# Sheet_WallSwitch_TOP.net
KiCad netlist of a schematic drawn in Altium Designer
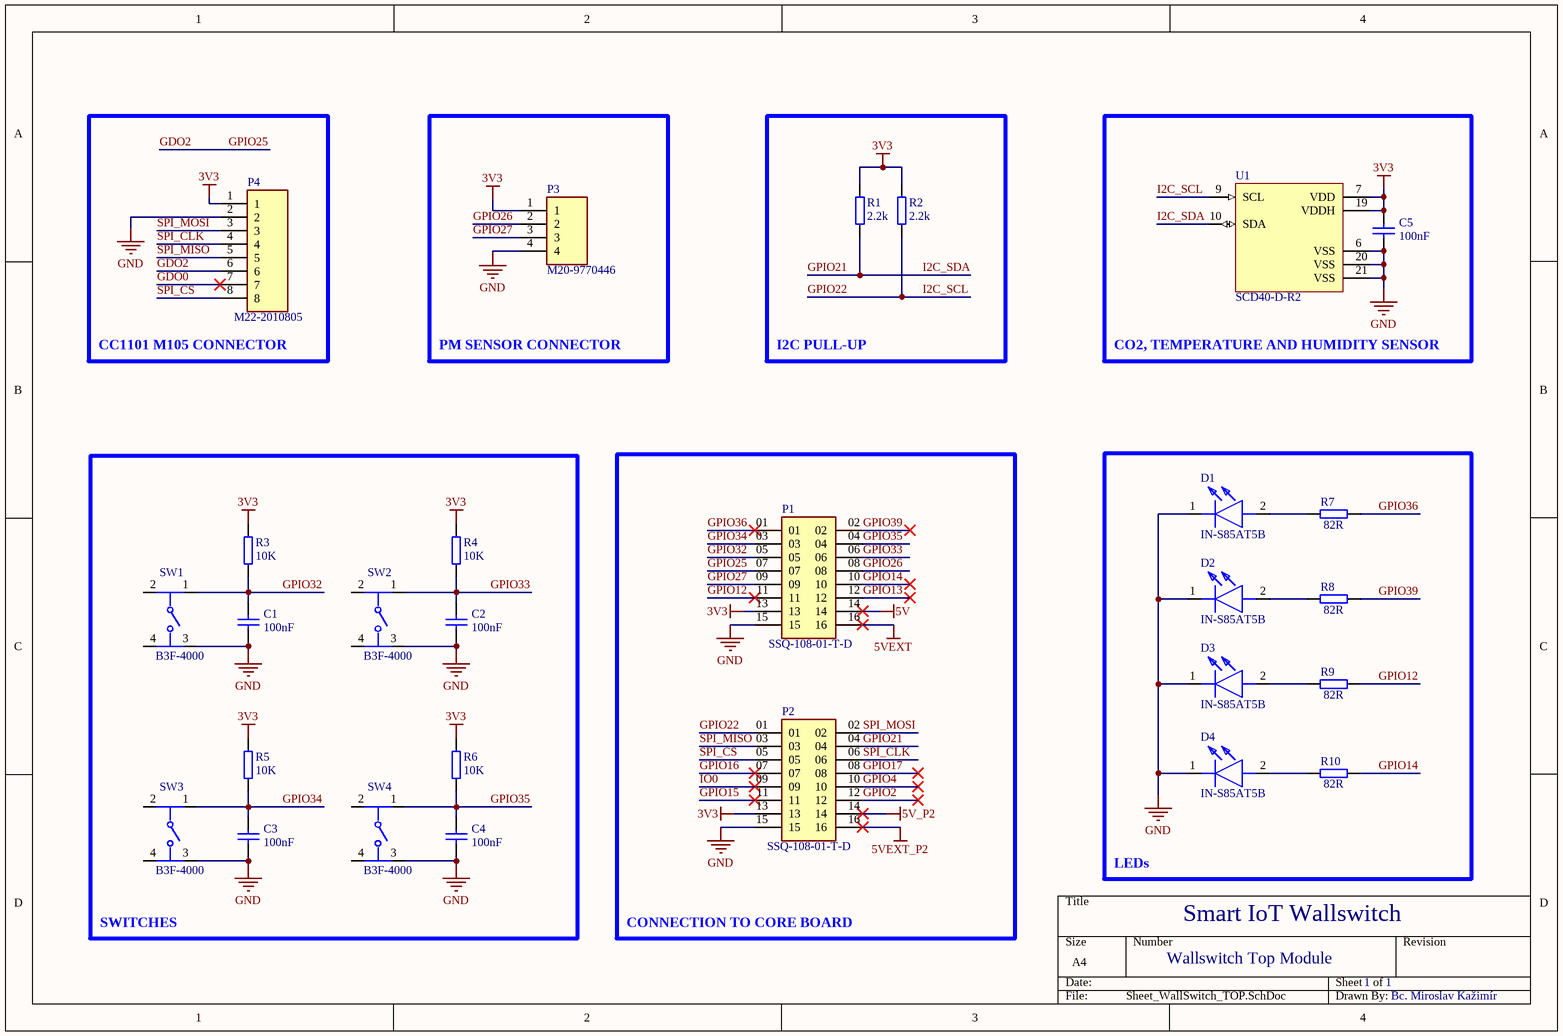
[diagram p0: Sheet_WallSwitch_TOP.SchDoc]

(export (version "E")
  (design (tool "Eeschema 10.0.6"))
  (components
    (comp (ref "C1")
      (value "C0805C104K5RAC7411")
      (footprint "FP-C0805C-DN-IPC_A")
      (description "Cap Ceramic 0.1uF 50V X7R 10% SMD 0805 125°C Paper T/R")
      (fields
        (field (name "MANUFACTURER") "KEMET")
        (field (name "TOLERANCE") "10%")
        (field (name "CAPACITANCE") "100nF")
      )
      (libsource (lib "Schlib1") (part "C0805C104K5RAC7411"))
    )
    (comp (ref "C2")
      (value "C0805C104K5RAC7411")
      (footprint "FP-C0805C-DN-IPC_A")
      (description "Cap Ceramic 0.1uF 50V X7R 10% SMD 0805 125°C Paper T/R")
      (fields
        (field (name "MANUFACTURER") "KEMET")
        (field (name "TOLERANCE") "10%")
        (field (name "CAPACITANCE") "100nF")
      )
      (libsource (lib "Schlib1") (part "C0805C104K5RAC7411"))
    )
    (comp (ref "C3")
      (value "C0805C104K5RAC7411")
      (footprint "FP-C0805C-DN-IPC_A")
      (description "Cap Ceramic 0.1uF 50V X7R 10% SMD 0805 125°C Paper T/R")
      (fields
        (field (name "MANUFACTURER") "KEMET")
        (field (name "TOLERANCE") "10%")
        (field (name "CAPACITANCE") "100nF")
      )
      (libsource (lib "Schlib1") (part "C0805C104K5RAC7411"))
    )
    (comp (ref "C4")
      (value "C0805C104K5RAC7411")
      (footprint "FP-C0805C-DN-IPC_A")
      (description "Cap Ceramic 0.1uF 50V X7R 10% SMD 0805 125°C Paper T/R")
      (fields
        (field (name "MANUFACTURER") "KEMET")
        (field (name "TOLERANCE") "10%")
        (field (name "CAPACITANCE") "100nF")
      )
      (libsource (lib "Schlib1") (part "C0805C104K5RAC7411"))
    )
    (comp (ref "C5")
      (value "C0805C104K5RAC7411")
      (footprint "FP-C0805C-DN-IPC_A")
      (description "Cap Ceramic 0.1uF 50V X7R 10% SMD 0805 125°C Paper T/R")
      (fields
        (field (name "MANUFACTURER") "KEMET")
        (field (name "TOLERANCE") "10%")
        (field (name "CAPACITANCE") "100nF")
      )
      (libsource (lib "Schlib1") (part "C0805C104K5RAC7411"))
    )
    (comp (ref "D1")
      (value "IN-S85AT5B")
      (footprint "LEDC2012X110N")
      (description "Led Blue Clear 0805 SMD")
      (fields (field (name "MANUFACTURER") "Inolux"))
      (libsource (lib "Schlib1") (part "IN-S85AT5B"))
    )
    (comp (ref "D2")
      (value "IN-S85AT5B")
      (footprint "LEDC2012X110N")
      (description "Led Blue Clear 0805 SMD")
      (fields (field (name "MANUFACTURER") "Inolux"))
      (libsource (lib "Schlib1") (part "IN-S85AT5B"))
    )
    (comp (ref "D3")
      (value "IN-S85AT5B")
      (footprint "LEDC2012X110N")
      (description "Led Blue Clear 0805 SMD")
      (fields (field (name "MANUFACTURER") "Inolux"))
      (libsource (lib "Schlib1") (part "IN-S85AT5B"))
    )
    (comp (ref "D4")
      (value "IN-S85AT5B")
      (footprint "LEDC2012X110N")
      (description "Led Blue Clear 0805 SMD")
      (fields (field (name "MANUFACTURER") "Inolux"))
      (libsource (lib "Schlib1") (part "IN-S85AT5B"))
    )
    (comp (ref "P1")
      (value "SSQ-108-01-T-D")
      (footprint "SAMTEC_SSQ-108-XX-X-D")
      (description "Headers & Wire Housings Tiger Buy Socket Strip with Square Tails, 0.100 Pitch")
      (fields (field (name "MANUFACTURER") "Samtec"))
      (libsource (lib "Schlib1") (part "SSQ-108-01-T-D"))
    )
    (comp (ref "P2")
      (value "SSQ-108-01-T-D")
      (footprint "SAMTEC_SSQ-108-XX-X-D")
      (description "Headers & Wire Housings Tiger Buy Socket Strip with Square Tails, 0.100 Pitch")
      (fields (field (name "MANUFACTURER") "Samtec"))
      (libsource (lib "Schlib1") (part "SSQ-108-01-T-D"))
    )
    (comp (ref "P3")
      (value "M20-9770446")
      (footprint "HDRV4W64P0X254_1X4_1016X254X834P")
      (description "04 SIL VERT PIN HDR")
      (fields (field (name "MANUFACTURER") "Harwin"))
      (libsource (lib "Schlib1") (part "M20-9770446"))
    )
    (comp (ref "P4")
      (value "M22-2010805")
      (footprint "HDRV8W60P0X200_1X8_1600X200X525P")
      (description "Connector, Header, 8Pos, 1Row, 2Mm Rohs Compliant: Yes")
      (fields (field (name "MANUFACTURER") "Harwin"))
      (libsource (lib "RPiZeroShield") (part "M22-2010805"))
    )
    (comp (ref "R1")
      (value "RCC12062K20FKEA")
      (footprint "RCC1206_e3")
      (description "Res, Aec-Q200, 2K2, 1%, 0.5W, 1206 Rohs Compliant: Yes")
      (fields (field (name "MANUFACTURER") "Vishay") (field (name "RESISTANCE") "2.2k"))
      (libsource (lib "Schlib1") (part "RCC12062K20FKEA"))
    )
    (comp (ref "R2")
      (value "RCC12062K20FKEA")
      (footprint "RCC1206_e3")
      (description "Res, Aec-Q200, 2K2, 1%, 0.5W, 1206 Rohs Compliant: Yes")
      (fields (field (name "MANUFACTURER") "Vishay") (field (name "RESISTANCE") "2.2k"))
      (libsource (lib "Schlib1") (part "RCC12062K20FKEA"))
    )
    (comp (ref "R3")
      (value "ERJ-UP6J103V")
      (footprint "RESC2012X70N")
      (description "Res 10K Ohm 5% 1/2W 0805")
      (fields (field (name "MANUFACTURER") "Panasonic") (field (name "RESISTANCE") "10K"))
      (libsource (lib "Schlib1") (part "ERJ-UP6J103V"))
    )
    (comp (ref "R4")
      (value "ERJ-UP6J103V")
      (footprint "RESC2012X70N")
      (description "Res 10K Ohm 5% 1/2W 0805")
      (fields (field (name "MANUFACTURER") "Panasonic") (field (name "RESISTANCE") "10K"))
      (libsource (lib "Schlib1") (part "ERJ-UP6J103V"))
    )
    (comp (ref "R5")
      (value "ERJ-UP6J103V")
      (footprint "RESC2012X70N")
      (description "Res 10K Ohm 5% 1/2W 0805")
      (fields (field (name "MANUFACTURER") "Panasonic") (field (name "RESISTANCE") "10K"))
      (libsource (lib "Schlib1") (part "ERJ-UP6J103V"))
    )
    (comp (ref "R6")
      (value "ERJ-UP6J103V")
      (footprint "RESC2012X70N")
      (description "Res 10K Ohm 5% 1/2W 0805")
      (fields (field (name "MANUFACTURER") "Panasonic") (field (name "RESISTANCE") "10K"))
      (libsource (lib "Schlib1") (part "ERJ-UP6J103V"))
    )
    (comp (ref "R7")
      (value "ESR10EZPJ820")
      (footprint "FP-ESR10-IPC_A")
      (description "Res Thick Film 0805 82 Ohm 5% 0.4W ±200ppm/C Epoxy Resin Pad SMD Automotive T/R")
      (fields
        (field (name "MANUFACTURER") "Rohm")
        (field (name "RESISTANCE") "82R")
        (field (name "TOLERANCE") "5%")
      )
      (libsource (lib "Schlib1") (part "ESR10EZPJ820"))
    )
    (comp (ref "R8")
      (value "ESR10EZPJ820")
      (footprint "FP-ESR10-IPC_A")
      (description "Res Thick Film 0805 82 Ohm 5% 0.4W ±200ppm/C Epoxy Resin Pad SMD Automotive T/R")
      (fields
        (field (name "MANUFACTURER") "Rohm")
        (field (name "RESISTANCE") "82R")
        (field (name "TOLERANCE") "5%")
      )
      (libsource (lib "Schlib1") (part "ESR10EZPJ820"))
    )
    (comp (ref "R9")
      (value "ESR10EZPJ820")
      (footprint "FP-ESR10-IPC_A")
      (description "Res Thick Film 0805 82 Ohm 5% 0.4W ±200ppm/C Epoxy Resin Pad SMD Automotive T/R")
      (fields
        (field (name "MANUFACTURER") "Rohm")
        (field (name "RESISTANCE") "82R")
        (field (name "TOLERANCE") "5%")
      )
      (libsource (lib "Schlib1") (part "ESR10EZPJ820"))
    )
    (comp (ref "R10")
      (value "ESR10EZPJ820")
      (footprint "FP-ESR10-IPC_A")
      (description "Res Thick Film 0805 82 Ohm 5% 0.4W ±200ppm/C Epoxy Resin Pad SMD Automotive T/R")
      (fields
        (field (name "MANUFACTURER") "Rohm")
        (field (name "RESISTANCE") "82R")
        (field (name "TOLERANCE") "5%")
      )
      (libsource (lib "Schlib1") (part "ESR10EZPJ820"))
    )
    (comp (ref "SW1")
      (value "B3F-4000")
      (footprint "FP-B3F-4000-MFG")
      (description "SWITCH TACTILE SPST-NO 0.05A 24V")
      (fields (field (name "MANUFACTURER") "Omron"))
      (libsource (lib "Schlib1") (part "B3F-4000"))
    )
    (comp (ref "SW2")
      (value "B3F-4000")
      (footprint "FP-B3F-4000-MFG")
      (description "SWITCH TACTILE SPST-NO 0.05A 24V")
      (fields (field (name "MANUFACTURER") "Omron"))
      (libsource (lib "Schlib1") (part "B3F-4000"))
    )
    (comp (ref "SW3")
      (value "B3F-4000")
      (footprint "FP-B3F-4000-MFG")
      (description "SWITCH TACTILE SPST-NO 0.05A 24V")
      (fields (field (name "MANUFACTURER") "Omron"))
      (libsource (lib "Schlib1") (part "B3F-4000"))
    )
    (comp (ref "SW4")
      (value "B3F-4000")
      (footprint "FP-B3F-4000-MFG")
      (description "SWITCH TACTILE SPST-NO 0.05A 24V")
      (fields (field (name "MANUFACTURER") "Omron"))
      (libsource (lib "Schlib1") (part "B3F-4000"))
    )
    (comp (ref "U1")
      (value "SCD40-D-R2")
      (footprint "SCD4x")
      (description "SCD40-D-R2 CO2 Sensor I2C, SMD ToR 600 pcs")
      (fields (field (name "MANUFACTURER") "Sensirion"))
      (libsource (lib "Schlib1") (part "SCD40-D-R2"))
    )
  )
  (nets
    (net (code "1") (name "/GDO0") (class "Default")
      (node (ref "P4") (pin "7") (pinfunction "7_7") (pintype "passive+no_connect"))
    )
    (net (code "2") (name "/GDO2") (class "Default")
      (node (ref "P1") (pin "07") (pinfunction "07_07") (pintype "passive"))
      (node (ref "P4") (pin "6") (pinfunction "6_6") (pintype "passive"))
    )
    (net (code "3") (name "/GPIO2") (class "Default")
      (node (ref "P2") (pin "12") (pinfunction "12_12") (pintype "passive+no_connect"))
    )
    (net (code "4") (name "/GPIO4") (class "Default")
      (node (ref "P2") (pin "10") (pinfunction "10_10") (pintype "passive+no_connect"))
    )
    (net (code "5") (name "/GPIO12") (class "Default")
      (node (ref "P1") (pin "11") (pinfunction "11_11") (pintype "passive"))
      (node (ref "R9") (pin "2") (pinfunction "2_2") (pintype "passive"))
    )
    (net (code "6") (name "/GPIO13") (class "Default")
      (node (ref "P1") (pin "12") (pinfunction "12_12") (pintype "passive+no_connect"))
    )
    (net (code "7") (name "/GPIO14") (class "Default")
      (node (ref "P1") (pin "10") (pinfunction "10_10") (pintype "passive"))
      (node (ref "R10") (pin "2") (pinfunction "2_2") (pintype "passive"))
    )
    (net (code "8") (name "/GPIO15") (class "Default")
      (node (ref "P2") (pin "11") (pinfunction "11_11") (pintype "passive+no_connect"))
    )
    (net (code "9") (name "/GPIO16") (class "Default")
      (node (ref "P2") (pin "07") (pinfunction "07_07") (pintype "passive+no_connect"))
    )
    (net (code "10") (name "/GPIO17") (class "Default")
      (node (ref "P2") (pin "08") (pinfunction "08_08") (pintype "passive+no_connect"))
    )
    (net (code "11") (name "/GPIO21") (class "Default")
      (node (ref "P2") (pin "04") (pinfunction "04_04") (pintype "passive"))
      (node (ref "R1") (pin "1") (pinfunction "1_1") (pintype "passive"))
      (node (ref "U1") (pin "10") (pinfunction "SDA_10") (pintype "bidirectional"))
    )
    (net (code "12") (name "/GPIO22") (class "Default")
      (node (ref "P2") (pin "01") (pinfunction "01_01") (pintype "passive"))
      (node (ref "R2") (pin "1") (pinfunction "1_1") (pintype "passive"))
      (node (ref "U1") (pin "9") (pinfunction "SCL_9") (pintype "input"))
    )
    (net (code "13") (name "/GPIO26") (class "Default")
      (node (ref "P1") (pin "08") (pinfunction "08_08") (pintype "passive"))
      (node (ref "P3") (pin "2") (pinfunction "2_2") (pintype "passive"))
    )
    (net (code "14") (name "/GPIO27") (class "Default")
      (node (ref "P1") (pin "09") (pinfunction "09_09") (pintype "passive"))
      (node (ref "P3") (pin "3") (pinfunction "3_3") (pintype "passive"))
    )
    (net (code "15") (name "/GPIO32") (class "Default")
      (node (ref "C1") (pin "1") (pinfunction "1_1") (pintype "passive"))
      (node (ref "P1") (pin "05") (pinfunction "05_05") (pintype "passive"))
      (node (ref "R3") (pin "2") (pinfunction "2_2") (pintype "passive"))
      (node (ref "SW1") (pin "1") (pinfunction "1_1") (pintype "passive"))
    )
    (net (code "16") (name "/GPIO33") (class "Default")
      (node (ref "C2") (pin "1") (pinfunction "1_1") (pintype "passive"))
      (node (ref "P1") (pin "06") (pinfunction "06_06") (pintype "passive"))
      (node (ref "R4") (pin "2") (pinfunction "2_2") (pintype "passive"))
      (node (ref "SW2") (pin "1") (pinfunction "1_1") (pintype "passive"))
    )
    (net (code "17") (name "/GPIO34") (class "Default")
      (node (ref "C3") (pin "1") (pinfunction "1_1") (pintype "passive"))
      (node (ref "P1") (pin "03") (pinfunction "03_03") (pintype "passive"))
      (node (ref "R5") (pin "2") (pinfunction "2_2") (pintype "passive"))
      (node (ref "SW3") (pin "1") (pinfunction "1_1") (pintype "passive"))
    )
    (net (code "18") (name "/GPIO35") (class "Default")
      (node (ref "C4") (pin "1") (pinfunction "1_1") (pintype "passive"))
      (node (ref "P1") (pin "04") (pinfunction "04_04") (pintype "passive"))
      (node (ref "R6") (pin "2") (pinfunction "2_2") (pintype "passive"))
      (node (ref "SW4") (pin "1") (pinfunction "1_1") (pintype "passive"))
    )
    (net (code "19") (name "/GPIO36") (class "Default")
      (node (ref "P1") (pin "01") (pinfunction "01_01") (pintype "passive"))
      (node (ref "R7") (pin "2") (pinfunction "2_2") (pintype "passive"))
    )
    (net (code "20") (name "/GPIO39") (class "Default")
      (node (ref "P1") (pin "02") (pinfunction "02_02") (pintype "passive"))
      (node (ref "R8") (pin "2") (pinfunction "2_2") (pintype "passive"))
    )
    (net (code "21") (name "/IO0") (class "Default")
      (node (ref "P2") (pin "09") (pinfunction "09_09") (pintype "passive+no_connect"))
    )
    (net (code "22") (name "/SPI_CLK") (class "Default")
      (node (ref "P2") (pin "06") (pinfunction "06_06") (pintype "passive"))
      (node (ref "P4") (pin "4") (pinfunction "4_4") (pintype "passive"))
    )
    (net (code "23") (name "/SPI_CS") (class "Default")
      (node (ref "P2") (pin "05") (pinfunction "05_05") (pintype "passive"))
      (node (ref "P4") (pin "8") (pinfunction "8_8") (pintype "passive"))
    )
    (net (code "24") (name "/SPI_MISO") (class "Default")
      (node (ref "P2") (pin "03") (pinfunction "03_03") (pintype "passive"))
      (node (ref "P4") (pin "5") (pinfunction "5_5") (pintype "passive"))
    )
    (net (code "25") (name "/SPI_MOSI") (class "Default")
      (node (ref "P2") (pin "02") (pinfunction "02_02") (pintype "passive"))
      (node (ref "P4") (pin "3") (pinfunction "3_3") (pintype "passive"))
    )
    (net (code "26") (name "3V3") (class "Default")
      (node (ref "C5") (pin "1") (pinfunction "1_1") (pintype "passive"))
      (node (ref "P1") (pin "13") (pinfunction "13_13") (pintype "passive"))
      (node (ref "P2") (pin "13") (pinfunction "13_13") (pintype "passive"))
      (node (ref "P3") (pin "1") (pinfunction "1_1") (pintype "passive"))
      (node (ref "P4") (pin "1") (pinfunction "1_1") (pintype "passive"))
      (node (ref "R1") (pin "2") (pinfunction "2_2") (pintype "passive"))
      (node (ref "R2") (pin "2") (pinfunction "2_2") (pintype "passive"))
      (node (ref "R3") (pin "1") (pinfunction "1_1") (pintype "passive"))
      (node (ref "R4") (pin "1") (pinfunction "1_1") (pintype "passive"))
      (node (ref "R5") (pin "1") (pinfunction "1_1") (pintype "passive"))
      (node (ref "R6") (pin "1") (pinfunction "1_1") (pintype "passive"))
      (node (ref "U1") (pin "19") (pinfunction "VDDH_19") (pintype "power_in"))
      (node (ref "U1") (pin "7") (pinfunction "VDD_7") (pintype "power_in"))
    )
    (net (code "27") (name "5V") (class "Default")
      (node (ref "P1") (pin "14") (pinfunction "14_14") (pintype "passive"))
    )
    (net (code "28") (name "5VEXT") (class "Default")
      (node (ref "P1") (pin "16") (pinfunction "16_16") (pintype "passive"))
    )
    (net (code "29") (name "5VEXT_P2") (class "Default")
      (node (ref "P2") (pin "16") (pinfunction "16_16") (pintype "passive"))
    )
    (net (code "30") (name "5V_P2") (class "Default")
      (node (ref "P2") (pin "14") (pinfunction "14_14") (pintype "passive"))
    )
    (net (code "31") (name "GND") (class "Default")
      (node (ref "C1") (pin "2") (pinfunction "2_2") (pintype "passive"))
      (node (ref "C2") (pin "2") (pinfunction "2_2") (pintype "passive"))
      (node (ref "C3") (pin "2") (pinfunction "2_2") (pintype "passive"))
      (node (ref "C4") (pin "2") (pinfunction "2_2") (pintype "passive"))
      (node (ref "C5") (pin "2") (pinfunction "2_2") (pintype "passive"))
      (node (ref "D1") (pin "1") (pinfunction "K_1") (pintype "passive"))
      (node (ref "D2") (pin "1") (pinfunction "K_1") (pintype "passive"))
      (node (ref "D3") (pin "1") (pinfunction "K_1") (pintype "passive"))
      (node (ref "D4") (pin "1") (pinfunction "K_1") (pintype "passive"))
      (node (ref "P1") (pin "15") (pinfunction "15_15") (pintype "passive"))
      (node (ref "P2") (pin "15") (pinfunction "15_15") (pintype "passive"))
      (node (ref "P3") (pin "4") (pinfunction "4_4") (pintype "passive"))
      (node (ref "P4") (pin "2") (pinfunction "2_2") (pintype "passive"))
      (node (ref "SW1") (pin "3") (pinfunction "3_3") (pintype "passive"))
      (node (ref "SW2") (pin "3") (pinfunction "3_3") (pintype "passive"))
      (node (ref "SW3") (pin "3") (pinfunction "3_3") (pintype "passive"))
      (node (ref "SW4") (pin "3") (pinfunction "3_3") (pintype "passive"))
      (node (ref "U1") (pin "20") (pinfunction "VSS_20") (pintype "power_in"))
      (node (ref "U1") (pin "21") (pinfunction "VSS_21") (pintype "power_in"))
      (node (ref "U1") (pin "6") (pinfunction "VSS_6") (pintype "power_in"))
    )
    (net (code "32") (name "Net-(D1-A)") (class "Default")
      (node (ref "D1") (pin "2") (pinfunction "A_2") (pintype "passive"))
      (node (ref "R7") (pin "1") (pinfunction "1_1") (pintype "passive"))
    )
    (net (code "33") (name "Net-(D2-A)") (class "Default")
      (node (ref "D2") (pin "2") (pinfunction "A_2") (pintype "passive"))
      (node (ref "R8") (pin "1") (pinfunction "1_1") (pintype "passive"))
    )
    (net (code "34") (name "Net-(D3-A)") (class "Default")
      (node (ref "D3") (pin "2") (pinfunction "A_2") (pintype "passive"))
      (node (ref "R9") (pin "1") (pinfunction "1_1") (pintype "passive"))
    )
    (net (code "35") (name "Net-(D4-A)") (class "Default")
      (node (ref "D4") (pin "2") (pinfunction "A_2") (pintype "passive"))
      (node (ref "R10") (pin "1") (pinfunction "1_1") (pintype "passive"))
    )
    (net (code "36") (name "unconnected-(SW1-Pad2)") (class "Default")
      (node (ref "SW1") (pin "2") (pinfunction "2_2") (pintype "passive"))
    )
    (net (code "37") (name "unconnected-(SW1-Pad4)") (class "Default")
      (node (ref "SW1") (pin "4") (pinfunction "4_4") (pintype "passive"))
    )
    (net (code "38") (name "unconnected-(SW2-Pad2)") (class "Default")
      (node (ref "SW2") (pin "2") (pinfunction "2_2") (pintype "passive"))
    )
    (net (code "39") (name "unconnected-(SW2-Pad4)") (class "Default")
      (node (ref "SW2") (pin "4") (pinfunction "4_4") (pintype "passive"))
    )
    (net (code "40") (name "unconnected-(SW3-Pad2)") (class "Default")
      (node (ref "SW3") (pin "2") (pinfunction "2_2") (pintype "passive"))
    )
    (net (code "41") (name "unconnected-(SW3-Pad4)") (class "Default")
      (node (ref "SW3") (pin "4") (pinfunction "4_4") (pintype "passive"))
    )
    (net (code "42") (name "unconnected-(SW4-Pad2)") (class "Default")
      (node (ref "SW4") (pin "2") (pinfunction "2_2") (pintype "passive"))
    )
    (net (code "43") (name "unconnected-(SW4-Pad4)") (class "Default")
      (node (ref "SW4") (pin "4") (pinfunction "4_4") (pintype "passive"))
    )
  )
)
